# boardpowersupply.net
KiCad netlist of a schematic drawn in EAGLE
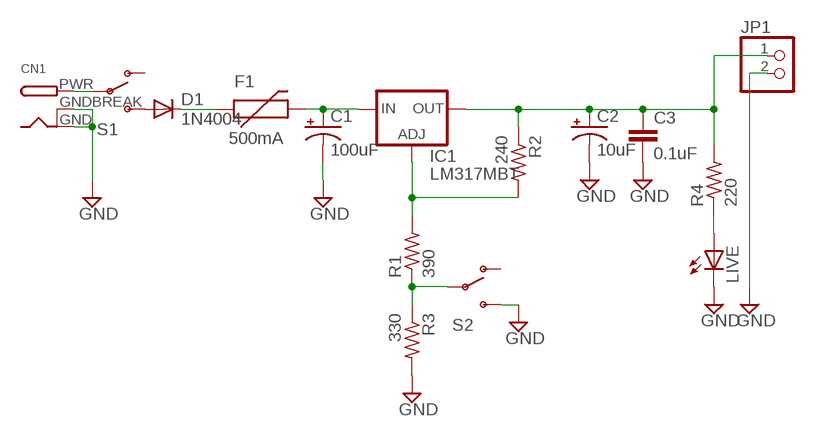
[diagram p0: schematic, sheet 1]

(export (version "E")
  (design (tool "Eeschema 10.0.6"))
  (components
    (comp (ref "C1")
      (value "100uF")
      (footprint "eagle-import:B45181A")
      (libsource (lib "eagle-import") (part "CPOL-USB45181A"))
    )
    (comp (ref "C2")
      (value "10uF")
      (footprint "eagle-import:B45181A")
      (libsource (lib "eagle-import") (part "CPOL-USB45181A"))
    )
    (comp (ref "C3")
      (value "0.1uF")
      (footprint "eagle-import:C2.5-2")
      (libsource (lib "eagle-import") (part "C2.5/2"))
    )
    (comp (ref "CN1")
      (value "DCBARRELPTH")
      (footprint "eagle-import:DCJACK_2MM_PTH")
      (libsource (lib "eagle-import") (part "DCBARRELPTH"))
    )
    (comp (ref "D1")
      (value "1N4004")
      (footprint "eagle-import:DO41-10")
      (libsource (lib "eagle-import") (part "1N4004"))
    )
    (comp (ref "F1")
      (value "500mA")
      (footprint "eagle-import:PTC")
      (libsource (lib "eagle-import") (part "PTCPTH"))
    )
    (comp (ref "IC1")
      (value "LM317MBT")
      (footprint "eagle-import:TO220L1")
      (libsource (lib "eagle-import") (part "LM317?MBT"))
    )
    (comp (ref "JP1")
      (value "PINHD-1X2")
      (footprint "eagle-import:1X02")
      (libsource (lib "eagle-import") (part "PINHD-1X2"))
    )
    (comp (ref "LIVE")
      (value "LED5MM")
      (footprint "eagle-import:LED5MM")
      (libsource (lib "eagle-import") (part "LED5MM"))
    )
    (comp (ref "R1")
      (value "390")
      (footprint "eagle-import:0204_7")
      (libsource (lib "eagle-import") (part "R-US_0204/7"))
    )
    (comp (ref "R2")
      (value "240")
      (footprint "eagle-import:0204_7")
      (libsource (lib "eagle-import") (part "R-US_0204/7"))
    )
    (comp (ref "R3")
      (value "330")
      (footprint "eagle-import:0204_7")
      (libsource (lib "eagle-import") (part "R-US_0204/7"))
    )
    (comp (ref "R4")
      (value "220")
      (footprint "eagle-import:0204_7")
      (libsource (lib "eagle-import") (part "R-US_0204/7"))
    )
    (comp (ref "S1")
      (value "SWITCH-SPDTKIT")
      (footprint "eagle-import:SWITCH-SPDT_KIT")
      (libsource (lib "eagle-import") (part "SWITCH-SPDTKIT"))
    )
    (comp (ref "S2")
      (value "SWITCH-SPDTKIT")
      (footprint "eagle-import:SWITCH-SPDT_KIT")
      (libsource (lib "eagle-import") (part "SWITCH-SPDTKIT"))
    )
  )
  (nets
    (net (code "1") (name "GND") (class "Default")
      (node (ref "C1") (pin "-") (pinfunction "-_-") (pintype "passive"))
      (node (ref "C2") (pin "-") (pinfunction "-_-") (pintype "passive"))
      (node (ref "C3") (pin "2") (pinfunction "2_2") (pintype "passive"))
      (node (ref "CN1") (pin "GND") (pinfunction "GND_GND") (pintype "power_in"))
      (node (ref "CN1") (pin "GNDBREAK") (pinfunction "GNDBREAK_GNDBREAK") (pintype "power_in"))
      (node (ref "JP1") (pin "2") (pinfunction "2_2") (pintype "passive"))
      (node (ref "LIVE") (pin "K") (pinfunction "C_K") (pintype "passive"))
      (node (ref "R3") (pin "2") (pinfunction "2_2") (pintype "passive"))
      (node (ref "S2") (pin "3") (pinfunction "S_3") (pintype "passive"))
    )
    (net (code "2") (name "Net-(F1-1)") (class "Default")
      (node (ref "D1") (pin "C") (pinfunction "C_C") (pintype "passive"))
      (node (ref "F1") (pin "P$1") (pinfunction "1_P$1") (pintype "bidirectional"))
    )
    (net (code "3") (name "Net-(F1-2)") (class "Default")
      (node (ref "C1") (pin "+") (pinfunction "+_+") (pintype "passive"))
      (node (ref "F1") (pin "P$2") (pinfunction "2_P$2") (pintype "bidirectional"))
      (node (ref "IC1") (pin "3") (pinfunction "IN_3") (pintype "input"))
    )
    (net (code "4") (name "Net-(IC1-ADJ)") (class "Default")
      (node (ref "IC1") (pin "1") (pinfunction "ADJ_1") (pintype "input"))
      (node (ref "R1") (pin "2") (pinfunction "2_2") (pintype "passive"))
      (node (ref "R2") (pin "2") (pinfunction "2_2") (pintype "passive"))
    )
    (net (code "5") (name "Net-(IC1-OUT)") (class "Default")
      (node (ref "C2") (pin "+") (pinfunction "+_+") (pintype "passive"))
      (node (ref "C3") (pin "1") (pinfunction "1_1") (pintype "passive"))
      (node (ref "IC1") (pin "2") (pinfunction "OUT_2") (pintype "passive"))
      (node (ref "JP1") (pin "1") (pinfunction "1_1") (pintype "passive"))
      (node (ref "R2") (pin "1") (pinfunction "1_1") (pintype "passive"))
      (node (ref "R4") (pin "2") (pinfunction "2_2") (pintype "passive"))
    )
    (net (code "6") (name "Net-(LIVE-PadA)") (class "Default")
      (node (ref "LIVE") (pin "A") (pinfunction "A_A") (pintype "passive"))
      (node (ref "R4") (pin "1") (pinfunction "1_1") (pintype "passive"))
    )
    (net (code "7") (name "Net-(S1-P)") (class "Default")
      (node (ref "CN1") (pin "PWR") (pinfunction "PWR_PWR") (pintype "power_in"))
      (node (ref "S1") (pin "2") (pinfunction "P_2") (pintype "passive"))
    )
    (net (code "8") (name "Net-(S1-S)") (class "Default")
      (node (ref "D1") (pin "A") (pinfunction "A_A") (pintype "passive"))
      (node (ref "S1") (pin "3") (pinfunction "S_3") (pintype "passive"))
    )
    (net (code "9") (name "Net-(S2-P)") (class "Default")
      (node (ref "R1") (pin "1") (pinfunction "1_1") (pintype "passive"))
      (node (ref "R3") (pin "1") (pinfunction "1_1") (pintype "passive"))
      (node (ref "S2") (pin "2") (pinfunction "P_2") (pintype "passive"))
    )
    (net (code "10") (name "unconnected-(S1-O-Pad1)") (class "Default")
      (node (ref "S1") (pin "1") (pinfunction "O_1") (pintype "passive"))
    )
    (net (code "11") (name "unconnected-(S2-O-Pad1)") (class "Default")
      (node (ref "S2") (pin "1") (pinfunction "O_1") (pintype "passive"))
    )
  )
)
